# mcp23017_sample.net
KiCad netlist of a schematic drawn in EAGLE
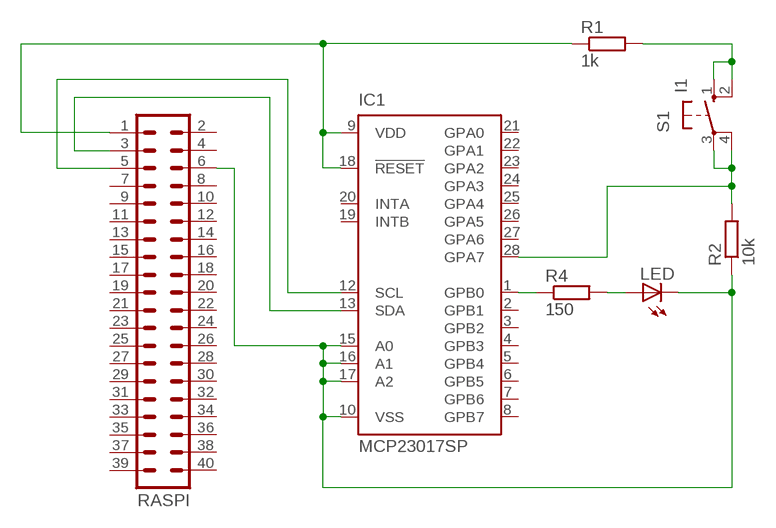
[diagram p0: schematic, sheet 1]

(export (version "E")
  (design (tool "Eeschema 10.0.6"))
  (components
    (comp (ref "IC1")
      (value "MCP23017SP")
      (footprint "eagle-import:DIL28-3")
      (fields (field (name "MF") "MICROCHIP") (field (name "MPN") "MCP23017-E/SP"))
      (libsource (lib "eagle-import") (part "MCP23017SP"))
    )
    (comp (ref "LED")
      (value "LED5MM")
      (footprint "eagle-import:LED5MM")
      (libsource (lib "eagle-import") (part "LED5MM"))
    )
    (comp (ref "R1")
      (value "1k")
      (footprint "eagle-import:0207_10")
      (libsource (lib "eagle-import") (part "R-EU_0207/10"))
    )
    (comp (ref "R2")
      (value "10k")
      (footprint "eagle-import:0207_10")
      (libsource (lib "eagle-import") (part "R-EU_0207/10"))
    )
    (comp (ref "R4")
      (value "150")
      (footprint "eagle-import:0207_10")
      (libsource (lib "eagle-import") (part "R-EU_0207/10"))
    )
    (comp (ref "RASPI")
      (value "ML40")
      (footprint "eagle-import:ML40")
      (libsource (lib "eagle-import") (part "ML40"))
    )
    (comp (ref "S1")
      (value "I1")
      (footprint "eagle-import:B3F-10XX")
      (fields (field (name "MPN") "B3F-1000"))
      (libsource (lib "eagle-import") (part "10-XX"))
    )
  )
  (nets
    (net (code "1") (name "Net-(IC1-A0)") (class "Default")
      (node (ref "IC1") (pin "10") (pinfunction "VSS_10") (pintype "power_in"))
      (node (ref "IC1") (pin "15") (pinfunction "A0_15") (pintype "input"))
      (node (ref "IC1") (pin "16") (pinfunction "A1_16") (pintype "input"))
      (node (ref "IC1") (pin "17") (pinfunction "A2_17") (pintype "input"))
      (node (ref "LED") (pin "K") (pinfunction "C_K") (pintype "passive"))
      (node (ref "R2") (pin "1") (pinfunction "1_1") (pintype "passive"))
      (node (ref "RASPI") (pin "6") (pinfunction "6_6") (pintype "passive"))
    )
    (net (code "2") (name "Net-(IC1-GPA7)") (class "Default")
      (node (ref "IC1") (pin "28") (pinfunction "GPA7_28") (pintype "bidirectional"))
      (node (ref "R2") (pin "2") (pinfunction "2_2") (pintype "passive"))
      (node (ref "S1") (pin "3") (pinfunction "P_3") (pintype "passive"))
      (node (ref "S1") (pin "4") (pinfunction "P1_4") (pintype "passive"))
    )
    (net (code "3") (name "Net-(IC1-GPB0)") (class "Default")
      (node (ref "IC1") (pin "1") (pinfunction "GPB0_1") (pintype "bidirectional"))
      (node (ref "R4") (pin "1") (pinfunction "1_1") (pintype "passive"))
    )
    (net (code "4") (name "Net-(IC1-SCL)") (class "Default")
      (node (ref "IC1") (pin "12") (pinfunction "SCL_12") (pintype "input"))
      (node (ref "RASPI") (pin "5") (pinfunction "5_5") (pintype "passive"))
    )
    (net (code "5") (name "Net-(IC1-SDA)") (class "Default")
      (node (ref "IC1") (pin "13") (pinfunction "SDA_13") (pintype "bidirectional"))
      (node (ref "RASPI") (pin "3") (pinfunction "3_3") (pintype "passive"))
    )
    (net (code "6") (name "Net-(IC1-VDD)") (class "Default")
      (node (ref "IC1") (pin "18") (pinfunction "~{RESET}_18") (pintype "input"))
      (node (ref "IC1") (pin "9") (pinfunction "VDD_9") (pintype "power_in"))
      (node (ref "R1") (pin "1") (pinfunction "1_1") (pintype "passive"))
      (node (ref "RASPI") (pin "1") (pinfunction "1_1") (pintype "passive"))
    )
    (net (code "7") (name "Net-(LED-PadA)") (class "Default")
      (node (ref "LED") (pin "A") (pinfunction "A_A") (pintype "passive"))
      (node (ref "R4") (pin "2") (pinfunction "2_2") (pintype "passive"))
    )
    (net (code "8") (name "Net-(S1-S)") (class "Default")
      (node (ref "R1") (pin "2") (pinfunction "2_2") (pintype "passive"))
      (node (ref "S1") (pin "1") (pinfunction "S_1") (pintype "passive"))
      (node (ref "S1") (pin "2") (pinfunction "S1_2") (pintype "passive"))
    )
    (net (code "9") (name "unconnected-(IC1-GPA0-Pad21)") (class "Default")
      (node (ref "IC1") (pin "21") (pinfunction "GPA0_21") (pintype "bidirectional"))
    )
    (net (code "10") (name "unconnected-(IC1-GPA1-Pad22)") (class "Default")
      (node (ref "IC1") (pin "22") (pinfunction "GPA1_22") (pintype "bidirectional"))
    )
    (net (code "11") (name "unconnected-(IC1-GPA2-Pad23)") (class "Default")
      (node (ref "IC1") (pin "23") (pinfunction "GPA2_23") (pintype "bidirectional"))
    )
    (net (code "12") (name "unconnected-(IC1-GPA3-Pad24)") (class "Default")
      (node (ref "IC1") (pin "24") (pinfunction "GPA3_24") (pintype "bidirectional"))
    )
    (net (code "13") (name "unconnected-(IC1-GPA4-Pad25)") (class "Default")
      (node (ref "IC1") (pin "25") (pinfunction "GPA4_25") (pintype "bidirectional"))
    )
    (net (code "14") (name "unconnected-(IC1-GPA5-Pad26)") (class "Default")
      (node (ref "IC1") (pin "26") (pinfunction "GPA5_26") (pintype "bidirectional"))
    )
    (net (code "15") (name "unconnected-(IC1-GPA6-Pad27)") (class "Default")
      (node (ref "IC1") (pin "27") (pinfunction "GPA6_27") (pintype "bidirectional"))
    )
    (net (code "16") (name "unconnected-(IC1-GPB1-Pad2)") (class "Default")
      (node (ref "IC1") (pin "2") (pinfunction "GPB1_2") (pintype "bidirectional"))
    )
    (net (code "17") (name "unconnected-(IC1-GPB2-Pad3)") (class "Default")
      (node (ref "IC1") (pin "3") (pinfunction "GPB2_3") (pintype "bidirectional"))
    )
    (net (code "18") (name "unconnected-(IC1-GPB3-Pad4)") (class "Default")
      (node (ref "IC1") (pin "4") (pinfunction "GPB3_4") (pintype "bidirectional"))
    )
    (net (code "19") (name "unconnected-(IC1-GPB4-Pad5)") (class "Default")
      (node (ref "IC1") (pin "5") (pinfunction "GPB4_5") (pintype "bidirectional"))
    )
    (net (code "20") (name "unconnected-(IC1-GPB5-Pad6)") (class "Default")
      (node (ref "IC1") (pin "6") (pinfunction "GPB5_6") (pintype "bidirectional"))
    )
    (net (code "21") (name "unconnected-(IC1-GPB6-Pad7)") (class "Default")
      (node (ref "IC1") (pin "7") (pinfunction "GPB6_7") (pintype "bidirectional"))
    )
    (net (code "22") (name "unconnected-(IC1-GPB7-Pad8)") (class "Default")
      (node (ref "IC1") (pin "8") (pinfunction "GPB7_8") (pintype "bidirectional"))
    )
    (net (code "23") (name "unconnected-(IC1-INTA-Pad20)") (class "Default")
      (node (ref "IC1") (pin "20") (pinfunction "INTA_20") (pintype "output"))
    )
    (net (code "24") (name "unconnected-(IC1-INTB-Pad19)") (class "Default")
      (node (ref "IC1") (pin "19") (pinfunction "INTB_19") (pintype "output"))
    )
    (net (code "25") (name "unconnected-(RASPI-Pad2)") (class "Default")
      (node (ref "RASPI") (pin "2") (pinfunction "2_2") (pintype "passive"))
    )
    (net (code "26") (name "unconnected-(RASPI-Pad4)") (class "Default")
      (node (ref "RASPI") (pin "4") (pinfunction "4_4") (pintype "passive"))
    )
    (net (code "27") (name "unconnected-(RASPI-Pad7)") (class "Default")
      (node (ref "RASPI") (pin "7") (pinfunction "7_7") (pintype "passive"))
    )
    (net (code "28") (name "unconnected-(RASPI-Pad8)") (class "Default")
      (node (ref "RASPI") (pin "8") (pinfunction "8_8") (pintype "passive"))
    )
    (net (code "29") (name "unconnected-(RASPI-Pad9)") (class "Default")
      (node (ref "RASPI") (pin "9") (pinfunction "9_9") (pintype "passive"))
    )
    (net (code "30") (name "unconnected-(RASPI-Pad10)") (class "Default")
      (node (ref "RASPI") (pin "10") (pinfunction "10_10") (pintype "passive"))
    )
    (net (code "31") (name "unconnected-(RASPI-Pad11)") (class "Default")
      (node (ref "RASPI") (pin "11") (pinfunction "11_11") (pintype "passive"))
    )
    (net (code "32") (name "unconnected-(RASPI-Pad12)") (class "Default")
      (node (ref "RASPI") (pin "12") (pinfunction "12_12") (pintype "passive"))
    )
    (net (code "33") (name "unconnected-(RASPI-Pad13)") (class "Default")
      (node (ref "RASPI") (pin "13") (pinfunction "13_13") (pintype "passive"))
    )
    (net (code "34") (name "unconnected-(RASPI-Pad14)") (class "Default")
      (node (ref "RASPI") (pin "14") (pinfunction "14_14") (pintype "passive"))
    )
    (net (code "35") (name "unconnected-(RASPI-Pad15)") (class "Default")
      (node (ref "RASPI") (pin "15") (pinfunction "15_15") (pintype "passive"))
    )
    (net (code "36") (name "unconnected-(RASPI-Pad16)") (class "Default")
      (node (ref "RASPI") (pin "16") (pinfunction "16_16") (pintype "passive"))
    )
    (net (code "37") (name "unconnected-(RASPI-Pad17)") (class "Default")
      (node (ref "RASPI") (pin "17") (pinfunction "17_17") (pintype "passive"))
    )
    (net (code "38") (name "unconnected-(RASPI-Pad18)") (class "Default")
      (node (ref "RASPI") (pin "18") (pinfunction "18_18") (pintype "passive"))
    )
    (net (code "39") (name "unconnected-(RASPI-Pad19)") (class "Default")
      (node (ref "RASPI") (pin "19") (pinfunction "19_19") (pintype "passive"))
    )
    (net (code "40") (name "unconnected-(RASPI-Pad20)") (class "Default")
      (node (ref "RASPI") (pin "20") (pinfunction "20_20") (pintype "passive"))
    )
    (net (code "41") (name "unconnected-(RASPI-Pad21)") (class "Default")
      (node (ref "RASPI") (pin "21") (pinfunction "21_21") (pintype "passive"))
    )
    (net (code "42") (name "unconnected-(RASPI-Pad22)") (class "Default")
      (node (ref "RASPI") (pin "22") (pinfunction "22_22") (pintype "passive"))
    )
    (net (code "43") (name "unconnected-(RASPI-Pad23)") (class "Default")
      (node (ref "RASPI") (pin "23") (pinfunction "23_23") (pintype "passive"))
    )
    (net (code "44") (name "unconnected-(RASPI-Pad24)") (class "Default")
      (node (ref "RASPI") (pin "24") (pinfunction "24_24") (pintype "passive"))
    )
    (net (code "45") (name "unconnected-(RASPI-Pad25)") (class "Default")
      (node (ref "RASPI") (pin "25") (pinfunction "25_25") (pintype "passive"))
    )
    (net (code "46") (name "unconnected-(RASPI-Pad26)") (class "Default")
      (node (ref "RASPI") (pin "26") (pinfunction "26_26") (pintype "passive"))
    )
    (net (code "47") (name "unconnected-(RASPI-Pad27)") (class "Default")
      (node (ref "RASPI") (pin "27") (pinfunction "27_27") (pintype "passive"))
    )
    (net (code "48") (name "unconnected-(RASPI-Pad28)") (class "Default")
      (node (ref "RASPI") (pin "28") (pinfunction "28_28") (pintype "passive"))
    )
    (net (code "49") (name "unconnected-(RASPI-Pad29)") (class "Default")
      (node (ref "RASPI") (pin "29") (pinfunction "29_29") (pintype "passive"))
    )
    (net (code "50") (name "unconnected-(RASPI-Pad30)") (class "Default")
      (node (ref "RASPI") (pin "30") (pinfunction "30_30") (pintype "passive"))
    )
    (net (code "51") (name "unconnected-(RASPI-Pad31)") (class "Default")
      (node (ref "RASPI") (pin "31") (pinfunction "31_31") (pintype "passive"))
    )
    (net (code "52") (name "unconnected-(RASPI-Pad32)") (class "Default")
      (node (ref "RASPI") (pin "32") (pinfunction "32_32") (pintype "passive"))
    )
    (net (code "53") (name "unconnected-(RASPI-Pad33)") (class "Default")
      (node (ref "RASPI") (pin "33") (pinfunction "33_33") (pintype "passive"))
    )
    (net (code "54") (name "unconnected-(RASPI-Pad34)") (class "Default")
      (node (ref "RASPI") (pin "34") (pinfunction "34_34") (pintype "passive"))
    )
    (net (code "55") (name "unconnected-(RASPI-Pad35)") (class "Default")
      (node (ref "RASPI") (pin "35") (pinfunction "35_35") (pintype "passive"))
    )
    (net (code "56") (name "unconnected-(RASPI-Pad36)") (class "Default")
      (node (ref "RASPI") (pin "36") (pinfunction "36_36") (pintype "passive"))
    )
    (net (code "57") (name "unconnected-(RASPI-Pad37)") (class "Default")
      (node (ref "RASPI") (pin "37") (pinfunction "37_37") (pintype "passive"))
    )
    (net (code "58") (name "unconnected-(RASPI-Pad38)") (class "Default")
      (node (ref "RASPI") (pin "38") (pinfunction "38_38") (pintype "passive"))
    )
    (net (code "59") (name "unconnected-(RASPI-Pad39)") (class "Default")
      (node (ref "RASPI") (pin "39") (pinfunction "39_39") (pintype "passive"))
    )
    (net (code "60") (name "unconnected-(RASPI-Pad40)") (class "Default")
      (node (ref "RASPI") (pin "40") (pinfunction "40_40") (pintype "passive"))
    )
  )
)
